# Microcontroller_1_1.net
KiCad netlist of a schematic drawn in EAGLE
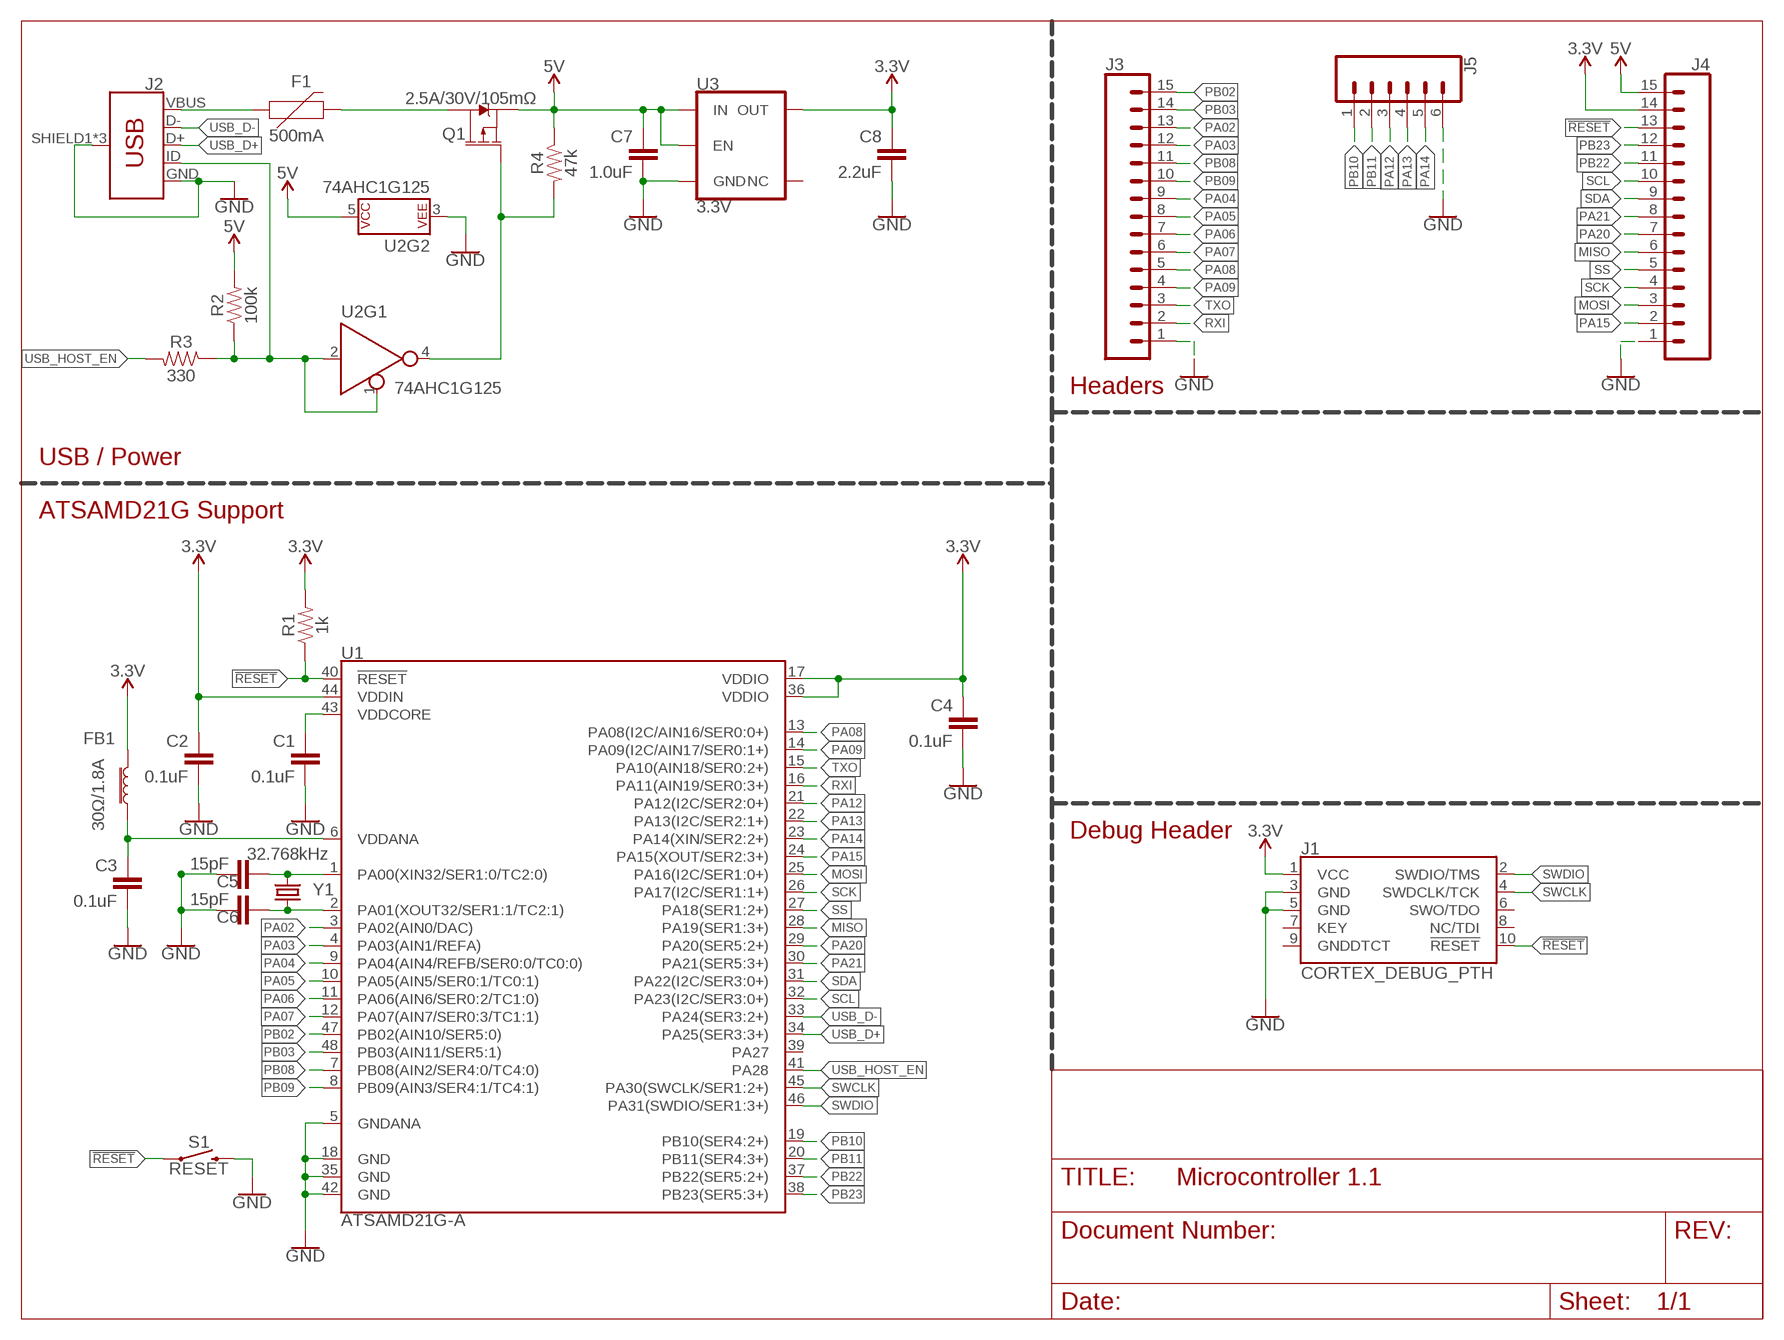
[diagram p0: schematic, sheet 1]

(export (version "E")
  (design (tool "Eeschema 10.0.6"))
  (components
    (comp (ref "C1")
      (value "0.1uF")
      (footprint "eagle-import:CAP-PTH-SMALL-KIT")
      (libsource (lib "eagle-import") (part "0.1UF-KIT-EZ-50V-20%"))
    )
    (comp (ref "C2")
      (value "0.1uF")
      (footprint "eagle-import:CAP-PTH-SMALL-KIT")
      (libsource (lib "eagle-import") (part "0.1UF-KIT-EZ-50V-20%"))
    )
    (comp (ref "C3")
      (value "0.1uF")
      (footprint "eagle-import:CAP-PTH-SMALL-KIT")
      (libsource (lib "eagle-import") (part "0.1UF-KIT-EZ-50V-20%"))
    )
    (comp (ref "C4")
      (value "0.1uF")
      (footprint "eagle-import:CAP-PTH-SMALL-KIT")
      (libsource (lib "eagle-import") (part "0.1UF-KIT-EZ-50V-20%"))
    )
    (comp (ref "C5")
      (value "15pF")
      (footprint "eagle-import:CAP-PTH-SMALL-KIT")
      (libsource (lib "eagle-import") (part "0.1UF-KIT-EZ-50V-20%"))
    )
    (comp (ref "C6")
      (value "15pF")
      (footprint "eagle-import:CAP-PTH-SMALL-KIT")
      (libsource (lib "eagle-import") (part "0.1UF-KIT-EZ-50V-20%"))
    )
    (comp (ref "C7")
      (value "1.0uF")
      (footprint "eagle-import:CAP-PTH-SMALL-KIT")
      (libsource (lib "eagle-import") (part "0.1UF-KIT-EZ-50V-20%"))
    )
    (comp (ref "C8")
      (value "2.2uF")
      (footprint "eagle-import:CAP-PTH-SMALL-KIT")
      (libsource (lib "eagle-import") (part "0.1UF-KIT-EZ-50V-20%"))
    )
    (comp (ref "F1")
      (value "500mA")
      (footprint "eagle-import:PTH")
      (libsource (lib "eagle-import") (part "PPTC_PTH"))
    )
    (comp (ref "FB1")
      (value "30Ω/1.8A")
      (footprint "eagle-import:0603")
      (libsource (lib "eagle-import") (part "FERRITE_BEAD-0603"))
    )
    (comp (ref "J1")
      (value "CORTEX_DEBUG_PTH")
      (footprint "eagle-import:2X5-PTH-1.27MM")
      (libsource (lib "eagle-import") (part "CORTEX_DEBUG_PTH"))
    )
    (comp (ref "J2")
      (value "USB_MICRO-B_FEMALE-SMT")
      (footprint "eagle-import:USB-B-MICRO-SMD")
      (libsource (lib "eagle-import") (part "USB_MICRO-B_FEMALE-SMT"))
    )
    (comp (ref "J3")
      (value "CONN_15LOCK")
      (footprint "eagle-import:1X15_LOCK")
      (libsource (lib "eagle-import") (part "CONN_15LOCK"))
    )
    (comp (ref "J4")
      (value "CONN_15LOCK")
      (footprint "eagle-import:1X15_LOCK")
      (libsource (lib "eagle-import") (part "CONN_15LOCK"))
    )
    (comp (ref "J5")
      (value "CONN_06LOCK")
      (footprint "eagle-import:1X06_LOCK")
      (libsource (lib "eagle-import") (part "CONN_06LOCK"))
    )
    (comp (ref "Q1")
      (value "2.5A/30V/105mΩ")
      (footprint "eagle-import:SOT23-3")
      (libsource (lib "eagle-import") (part "MOSFET_PCH-DMG2307L"))
    )
    (comp (ref "R1")
      (value "1k")
      (footprint "eagle-import:AXIAL-0.3")
      (libsource (lib "eagle-import") (part "1KOHM-HORIZ-1/4W-1%"))
    )
    (comp (ref "R2")
      (value "100k")
      (footprint "eagle-import:AXIAL-0.3")
      (libsource (lib "eagle-import") (part "1KOHM-HORIZ-1/4W-1%"))
    )
    (comp (ref "R3")
      (value "330")
      (footprint "eagle-import:AXIAL-0.3")
      (libsource (lib "eagle-import") (part "1KOHM-HORIZ-1/4W-1%"))
    )
    (comp (ref "R4")
      (value "47k")
      (footprint "eagle-import:AXIAL-0.3")
      (libsource (lib "eagle-import") (part "1KOHM-HORIZ-1/4W-1%"))
    )
    (comp (ref "S1")
      (value "RESET")
      (footprint "eagle-import:TACTILE_SWITCH_PTH_RIGHT_ANGLE_KIT")
      (libsource (lib "eagle-import") (part "MOMENTARY-SWITCH-SPST-PTH-RIGHT-ANGLE-KIT"))
    )
    (comp (ref "U1")
      (value "ATSAMD21G-A")
      (footprint "eagle-import:TQFP-48")
      (libsource (lib "eagle-import") (part "ATSAMD21G-A"))
    )
    (comp (ref "U2")
      (value "74AHC1G125")
      (footprint "eagle-import:SOT23-5")
      (libsource (lib "eagle-import") (part "741G125DAHC"))
    )
    (comp (ref "U3")
      (value "3.3V")
      (footprint "eagle-import:SOT23-5")
      (libsource (lib "eagle-import") (part "V_REG_AP2112K-3.3V"))
    )
    (comp (ref "Y1")
      (value "32.768kHz")
      (footprint "eagle-import:CRYSTAL-PTH-2X6-CYL")
      (libsource (lib "eagle-import") (part "CRYSTAL-32.768KHZPTH-2X6"))
    )
  )
  (nets
    (net (code "1") (name "/~{RESET}") (class "Default")
      (node (ref "J1") (pin "10") (pinfunction "~{RESET}_10") (pintype "bidirectional"))
      (node (ref "J4") (pin "13") (pinfunction "13_13") (pintype "passive"))
      (node (ref "R1") (pin "P$1") (pinfunction "1_P$1") (pintype "passive"))
      (node (ref "S1") (pin "1") (pinfunction "1_1") (pintype "passive"))
      (node (ref "U1") (pin "40") (pinfunction "~{RESET}_40") (pintype "bidirectional"))
    )
    (net (code "2") (name "3.3V") (class "Default")
      (node (ref "C2") (pin "1") (pinfunction "1_1") (pintype "passive"))
      (node (ref "C4") (pin "1") (pinfunction "1_1") (pintype "passive"))
      (node (ref "C8") (pin "1") (pinfunction "1_1") (pintype "passive"))
      (node (ref "FB1") (pin "1") (pinfunction "1_1") (pintype "passive"))
      (node (ref "J1") (pin "1") (pinfunction "VCC_1") (pintype "bidirectional"))
      (node (ref "J4") (pin "14") (pinfunction "14_14") (pintype "passive"))
      (node (ref "R1") (pin "P$2") (pinfunction "2_P$2") (pintype "passive"))
      (node (ref "U1") (pin "17") (pinfunction "VDDIO_17") (pintype "bidirectional"))
      (node (ref "U1") (pin "36") (pinfunction "VDDIO_36") (pintype "bidirectional"))
      (node (ref "U1") (pin "44") (pinfunction "VDDIN_44") (pintype "bidirectional"))
      (node (ref "U3") (pin "5") (pinfunction "OUT_5") (pintype "passive"))
    )
    (net (code "3") (name "5V") (class "Default")
      (node (ref "C7") (pin "1") (pinfunction "1_1") (pintype "passive"))
      (node (ref "J4") (pin "15") (pinfunction "15_15") (pintype "passive"))
      (node (ref "Q1") (pin "2") (pinfunction "S_2") (pintype "bidirectional"))
      (node (ref "R2") (pin "P$2") (pinfunction "2_P$2") (pintype "passive"))
      (node (ref "R4") (pin "P$1") (pinfunction "1_P$1") (pintype "passive"))
      (node (ref "U2") (pin "5") (pinfunction "P$V+_5") (pintype "bidirectional"))
      (node (ref "U3") (pin "1") (pinfunction "IN_1") (pintype "input"))
      (node (ref "U3") (pin "3") (pinfunction "EN_3") (pintype "input"))
    )
    (net (code "4") (name "GND") (class "Default")
      (node (ref "C1") (pin "2") (pinfunction "2_2") (pintype "passive"))
      (node (ref "C2") (pin "2") (pinfunction "2_2") (pintype "passive"))
      (node (ref "C3") (pin "2") (pinfunction "2_2") (pintype "passive"))
      (node (ref "C4") (pin "2") (pinfunction "2_2") (pintype "passive"))
      (node (ref "C5") (pin "1") (pinfunction "1_1") (pintype "passive"))
      (node (ref "C6") (pin "1") (pinfunction "1_1") (pintype "passive"))
      (node (ref "C7") (pin "2") (pinfunction "2_2") (pintype "passive"))
      (node (ref "C8") (pin "2") (pinfunction "2_2") (pintype "passive"))
      (node (ref "J1") (pin "3") (pinfunction "GND_3") (pintype "bidirectional"))
      (node (ref "J1") (pin "5") (pinfunction "GND_5") (pintype "bidirectional"))
      (node (ref "J2") (pin "GND") (pinfunction "GND_GND") (pintype "power_in"))
      (node (ref "J2") (pin "SHIELD1") (pinfunction "SHIELD_SHIELD1") (pintype "bidirectional"))
      (node (ref "J2") (pin "SHIELD2") (pinfunction "SHIELD_SHIELD2") (pintype "bidirectional"))
      (node (ref "J2") (pin "SHIELD3") (pinfunction "SHIELD_SHIELD3") (pintype "bidirectional"))
      (node (ref "J3") (pin "1") (pinfunction "1_1") (pintype "passive"))
      (node (ref "J4") (pin "1") (pinfunction "1_1") (pintype "passive"))
      (node (ref "J5") (pin "6") (pinfunction "6_6") (pintype "passive"))
      (node (ref "S1") (pin "2") (pinfunction "2_2") (pintype "passive"))
      (node (ref "U1") (pin "18") (pinfunction "GND_18") (pintype "bidirectional"))
      (node (ref "U1") (pin "35") (pinfunction "GND_35") (pintype "bidirectional"))
      (node (ref "U1") (pin "42") (pinfunction "GND_42") (pintype "bidirectional"))
      (node (ref "U1") (pin "5") (pinfunction "GNDANA_5") (pintype "bidirectional"))
      (node (ref "U2") (pin "3") (pinfunction "P$V-_3") (pintype "bidirectional"))
      (node (ref "U3") (pin "2") (pinfunction "GND_2") (pintype "input"))
    )
    (net (code "5") (name "MISO") (class "Default")
      (node (ref "J4") (pin "6") (pinfunction "6_6") (pintype "passive"))
      (node (ref "U1") (pin "28") (pinfunction "PA19(SER1:3+)_28") (pintype "bidirectional"))
    )
    (net (code "6") (name "MOSI") (class "Default")
      (node (ref "J4") (pin "3") (pinfunction "3_3") (pintype "passive"))
      (node (ref "U1") (pin "25") (pinfunction "PA16(I2C/SER1:0+)_25") (pintype "bidirectional"))
    )
    (net (code "7") (name "Net-(F1-1)") (class "Default")
      (node (ref "F1") (pin "P$1") (pinfunction "1_P$1") (pintype "bidirectional"))
      (node (ref "J2") (pin "VBUS") (pinfunction "VBUS_VBUS") (pintype "power_in"))
    )
    (net (code "8") (name "Net-(F1-2)") (class "Default")
      (node (ref "F1") (pin "P$2") (pinfunction "2_P$2") (pintype "bidirectional"))
      (node (ref "Q1") (pin "3") (pinfunction "D_3") (pintype "bidirectional"))
    )
    (net (code "9") (name "Net-(Q1-G)") (class "Default")
      (node (ref "Q1") (pin "1") (pinfunction "G_1") (pintype "bidirectional"))
      (node (ref "R4") (pin "P$2") (pinfunction "2_P$2") (pintype "passive"))
      (node (ref "U2") (pin "4") (pinfunction "Y_4") (pintype "bidirectional"))
    )
    (net (code "10") (name "Net-(R2-1)") (class "Default")
      (node (ref "J2") (pin "ID") (pinfunction "ID_ID") (pintype "bidirectional"))
      (node (ref "R2") (pin "P$1") (pinfunction "1_P$1") (pintype "passive"))
      (node (ref "R3") (pin "P$1") (pinfunction "1_P$1") (pintype "passive"))
      (node (ref "U2") (pin "1") (pinfunction "~{EN}_1") (pintype "bidirectional"))
      (node (ref "U2") (pin "2") (pinfunction "A_2") (pintype "bidirectional"))
    )
    (net (code "11") (name "Net-(U1-PA00(XIN32{slash}SER1:0{slash}TC2:0))") (class "Default")
      (node (ref "C5") (pin "2") (pinfunction "2_2") (pintype "passive"))
      (node (ref "U1") (pin "1") (pinfunction "PA00(XIN32/SER1:0/TC2:0)_1") (pintype "bidirectional"))
      (node (ref "Y1") (pin "2") (pinfunction "2_2") (pintype "passive"))
    )
    (net (code "12") (name "Net-(U1-PA01(XOUT32{slash}SER1:1{slash}TC2:1))") (class "Default")
      (node (ref "C6") (pin "2") (pinfunction "2_2") (pintype "passive"))
      (node (ref "U1") (pin "2") (pinfunction "PA01(XOUT32/SER1:1/TC2:1)_2") (pintype "bidirectional"))
      (node (ref "Y1") (pin "1") (pinfunction "1_1") (pintype "passive"))
    )
    (net (code "13") (name "Net-(U1-VDDANA)") (class "Default")
      (node (ref "C3") (pin "1") (pinfunction "1_1") (pintype "passive"))
      (node (ref "FB1") (pin "2") (pinfunction "2_2") (pintype "passive"))
      (node (ref "U1") (pin "6") (pinfunction "VDDANA_6") (pintype "bidirectional"))
    )
    (net (code "14") (name "Net-(U1-VDDCORE)") (class "Default")
      (node (ref "C1") (pin "1") (pinfunction "1_1") (pintype "passive"))
      (node (ref "U1") (pin "43") (pinfunction "VDDCORE_43") (pintype "bidirectional"))
    )
    (net (code "15") (name "PA02") (class "Default")
      (node (ref "J3") (pin "13") (pinfunction "13_13") (pintype "passive"))
      (node (ref "U1") (pin "3") (pinfunction "PA02(AIN0/DAC)_3") (pintype "bidirectional"))
    )
    (net (code "16") (name "PA03") (class "Default")
      (node (ref "J3") (pin "12") (pinfunction "12_12") (pintype "passive"))
      (node (ref "U1") (pin "4") (pinfunction "PA03(AIN1/REFA)_4") (pintype "bidirectional"))
    )
    (net (code "17") (name "PA04") (class "Default")
      (node (ref "J3") (pin "9") (pinfunction "9_9") (pintype "passive"))
      (node (ref "U1") (pin "9") (pinfunction "PA04(AIN4/REFB/SER0:0/TC0:0)_9") (pintype "bidirectional"))
    )
    (net (code "18") (name "PA05") (class "Default")
      (node (ref "J3") (pin "8") (pinfunction "8_8") (pintype "passive"))
      (node (ref "U1") (pin "10") (pinfunction "PA05(AIN5/SER0:1/TC0:1)_10") (pintype "bidirectional"))
    )
    (net (code "19") (name "PA06") (class "Default")
      (node (ref "J3") (pin "7") (pinfunction "7_7") (pintype "passive"))
      (node (ref "U1") (pin "11") (pinfunction "PA06(AIN6/SER0:2/TC1:0)_11") (pintype "bidirectional"))
    )
    (net (code "20") (name "PA07") (class "Default")
      (node (ref "J3") (pin "6") (pinfunction "6_6") (pintype "passive"))
      (node (ref "U1") (pin "12") (pinfunction "PA07(AIN7/SER0:3/TC1:1)_12") (pintype "bidirectional"))
    )
    (net (code "21") (name "PA08") (class "Default")
      (node (ref "J3") (pin "5") (pinfunction "5_5") (pintype "passive"))
      (node (ref "U1") (pin "13") (pinfunction "PA08(I2C/AIN16/SER0:0+)_13") (pintype "bidirectional"))
    )
    (net (code "22") (name "PA09") (class "Default")
      (node (ref "J3") (pin "4") (pinfunction "4_4") (pintype "passive"))
      (node (ref "U1") (pin "14") (pinfunction "PA09(I2C/AIN17/SER0:1+)_14") (pintype "bidirectional"))
    )
    (net (code "23") (name "PA12") (class "Default")
      (node (ref "J5") (pin "3") (pinfunction "3_3") (pintype "passive"))
      (node (ref "U1") (pin "21") (pinfunction "PA12(I2C/SER2:0+)_21") (pintype "bidirectional"))
    )
    (net (code "24") (name "PA13") (class "Default")
      (node (ref "J5") (pin "4") (pinfunction "4_4") (pintype "passive"))
      (node (ref "U1") (pin "22") (pinfunction "PA13(I2C/SER2:1+)_22") (pintype "bidirectional"))
    )
    (net (code "25") (name "PA14") (class "Default")
      (node (ref "J5") (pin "5") (pinfunction "5_5") (pintype "passive"))
      (node (ref "U1") (pin "23") (pinfunction "PA14(XIN/SER2:2+)_23") (pintype "bidirectional"))
    )
    (net (code "26") (name "PA15") (class "Default")
      (node (ref "J4") (pin "2") (pinfunction "2_2") (pintype "passive"))
      (node (ref "U1") (pin "24") (pinfunction "PA15(XOUT/SER2:3+)_24") (pintype "bidirectional"))
    )
    (net (code "27") (name "PA20") (class "Default")
      (node (ref "J4") (pin "7") (pinfunction "7_7") (pintype "passive"))
      (node (ref "U1") (pin "29") (pinfunction "PA20(SER5:2+)_29") (pintype "bidirectional"))
    )
    (net (code "28") (name "PA21") (class "Default")
      (node (ref "J4") (pin "8") (pinfunction "8_8") (pintype "passive"))
      (node (ref "U1") (pin "30") (pinfunction "PA21(SER5:3+)_30") (pintype "bidirectional"))
    )
    (net (code "29") (name "PB02") (class "Default")
      (node (ref "J3") (pin "15") (pinfunction "15_15") (pintype "passive"))
      (node (ref "U1") (pin "47") (pinfunction "PB02(AIN10/SER5:0)_47") (pintype "bidirectional"))
    )
    (net (code "30") (name "PB03") (class "Default")
      (node (ref "J3") (pin "14") (pinfunction "14_14") (pintype "passive"))
      (node (ref "U1") (pin "48") (pinfunction "PB03(AIN11/SER5:1)_48") (pintype "bidirectional"))
    )
    (net (code "31") (name "PB08") (class "Default")
      (node (ref "J3") (pin "11") (pinfunction "11_11") (pintype "passive"))
      (node (ref "U1") (pin "7") (pinfunction "PB08(AIN2/SER4:0/TC4:0)_7") (pintype "bidirectional"))
    )
    (net (code "32") (name "PB09") (class "Default")
      (node (ref "J3") (pin "10") (pinfunction "10_10") (pintype "passive"))
      (node (ref "U1") (pin "8") (pinfunction "PB09(AIN3/SER4:1/TC4:1)_8") (pintype "bidirectional"))
    )
    (net (code "33") (name "PB10") (class "Default")
      (node (ref "J5") (pin "1") (pinfunction "1_1") (pintype "passive"))
      (node (ref "U1") (pin "19") (pinfunction "PB10(SER4:2+)_19") (pintype "bidirectional"))
    )
    (net (code "34") (name "PB11") (class "Default")
      (node (ref "J5") (pin "2") (pinfunction "2_2") (pintype "passive"))
      (node (ref "U1") (pin "20") (pinfunction "PB11(SER4:3+)_20") (pintype "bidirectional"))
    )
    (net (code "35") (name "PB22") (class "Default")
      (node (ref "J4") (pin "11") (pinfunction "11_11") (pintype "passive"))
      (node (ref "U1") (pin "37") (pinfunction "PB22(SER5:2+)_37") (pintype "bidirectional"))
    )
    (net (code "36") (name "PB23") (class "Default")
      (node (ref "J4") (pin "12") (pinfunction "12_12") (pintype "passive"))
      (node (ref "U1") (pin "38") (pinfunction "PB23(SER5:3+)_38") (pintype "bidirectional"))
    )
    (net (code "37") (name "RXI") (class "Default")
      (node (ref "J3") (pin "2") (pinfunction "2_2") (pintype "passive"))
      (node (ref "U1") (pin "16") (pinfunction "PA11(AIN19/SER0:3+)_16") (pintype "bidirectional"))
    )
    (net (code "38") (name "SCK") (class "Default")
      (node (ref "J4") (pin "4") (pinfunction "4_4") (pintype "passive"))
      (node (ref "U1") (pin "26") (pinfunction "PA17(I2C/SER1:1+)_26") (pintype "bidirectional"))
    )
    (net (code "39") (name "SCL") (class "Default")
      (node (ref "J4") (pin "10") (pinfunction "10_10") (pintype "passive"))
      (node (ref "U1") (pin "32") (pinfunction "PA23(I2C/SER3:0+)_32") (pintype "bidirectional"))
    )
    (net (code "40") (name "SDA") (class "Default")
      (node (ref "J4") (pin "9") (pinfunction "9_9") (pintype "passive"))
      (node (ref "U1") (pin "31") (pinfunction "PA22(I2C/SER3:0+)_31") (pintype "bidirectional"))
    )
    (net (code "41") (name "SS") (class "Default")
      (node (ref "J4") (pin "5") (pinfunction "5_5") (pintype "passive"))
      (node (ref "U1") (pin "27") (pinfunction "PA18(SER1:2+)_27") (pintype "bidirectional"))
    )
    (net (code "42") (name "SWCLK") (class "Default")
      (node (ref "J1") (pin "4") (pinfunction "SWDCLK/TCK_4") (pintype "bidirectional"))
      (node (ref "U1") (pin "45") (pinfunction "PA30(SWCLK/SER1:2+)_45") (pintype "bidirectional"))
    )
    (net (code "43") (name "SWDIO") (class "Default")
      (node (ref "J1") (pin "2") (pinfunction "SWDIO/TMS_2") (pintype "bidirectional"))
      (node (ref "U1") (pin "46") (pinfunction "PA31(SWDIO/SER1:3+)_46") (pintype "bidirectional"))
    )
    (net (code "44") (name "TXO") (class "Default")
      (node (ref "J3") (pin "3") (pinfunction "3_3") (pintype "passive"))
      (node (ref "U1") (pin "15") (pinfunction "PA10(AIN18/SER0:2+)_15") (pintype "bidirectional"))
    )
    (net (code "45") (name "USB_D+") (class "Default")
      (node (ref "J2") (pin "D+") (pinfunction "D+_D+") (pintype "bidirectional"))
      (node (ref "U1") (pin "34") (pinfunction "PA25(SER3:3+)_34") (pintype "bidirectional"))
    )
    (net (code "46") (name "USB_D-") (class "Default")
      (node (ref "J2") (pin "D-") (pinfunction "D-_D-") (pintype "bidirectional"))
      (node (ref "U1") (pin "33") (pinfunction "PA24(SER3:2+)_33") (pintype "bidirectional"))
    )
    (net (code "47") (name "USB_HOST_EN") (class "Default")
      (node (ref "R3") (pin "P$2") (pinfunction "2_P$2") (pintype "passive"))
      (node (ref "U1") (pin "41") (pinfunction "PA28_41") (pintype "bidirectional"))
    )
    (net (code "48") (name "unconnected-(J1-GNDDTCT-Pad9)") (class "Default")
      (node (ref "J1") (pin "9") (pinfunction "GNDDTCT_9") (pintype "bidirectional"))
    )
    (net (code "49") (name "unconnected-(J1-KEY-Pad7)") (class "Default")
      (node (ref "J1") (pin "7") (pinfunction "KEY_7") (pintype "bidirectional"))
    )
    (net (code "50") (name "unconnected-(J1-NC{slash}TDI-Pad8)") (class "Default")
      (node (ref "J1") (pin "8") (pinfunction "NC/TDI_8") (pintype "bidirectional"))
    )
    (net (code "51") (name "unconnected-(J1-SWO{slash}TDO-Pad6)") (class "Default")
      (node (ref "J1") (pin "6") (pinfunction "SWO/TDO_6") (pintype "bidirectional"))
    )
    (net (code "52") (name "unconnected-(U1-PA27-Pad39)") (class "Default")
      (node (ref "U1") (pin "39") (pinfunction "PA27_39") (pintype "bidirectional"))
    )
    (net (code "53") (name "unconnected-(U3-NC-Pad4)") (class "Default")
      (node (ref "U3") (pin "4") (pinfunction "NC_4") (pintype "no_connect"))
    )
  )
)
